# Grove_-_Button_x2.net
KiCad netlist of a schematic drawn in EAGLE
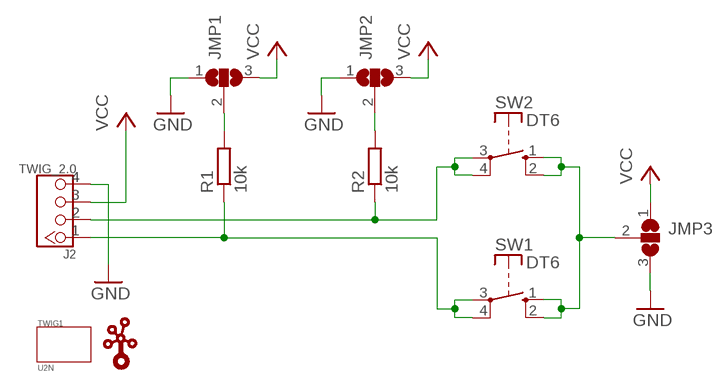
[diagram p0: schematic, sheet 1]

(export (version "E")
  (design (tool "Eeschema 10.0.6"))
  (components
    (comp (ref "J2")
      (value "TWIG_2.0")
      (footprint "eagle-import:2.0_1X4")
      (libsource (lib "eagle-import") (part "TWIG_2.0"))
    )
    (comp (ref "JMP1")
      (value "SJ2W")
      (footprint "eagle-import:SJ_2")
      (libsource (lib "eagle-import") (part "SJ2W"))
    )
    (comp (ref "JMP2")
      (value "SJ2W")
      (footprint "eagle-import:SJ_2")
      (libsource (lib "eagle-import") (part "SJ2W"))
    )
    (comp (ref "JMP3")
      (value "SJ2W")
      (footprint "eagle-import:SJ_2")
      (libsource (lib "eagle-import") (part "SJ2W"))
    )
    (comp (ref "R1")
      (value "10k")
      (footprint "eagle-import:R0805")
      (libsource (lib "eagle-import") (part "R-EU_R0805"))
    )
    (comp (ref "R2")
      (value "10k")
      (footprint "eagle-import:R0805")
      (libsource (lib "eagle-import") (part "R-EU_R0805"))
    )
    (comp (ref "SW1")
      (value "DT6")
      (footprint "eagle-import:DT6")
      (libsource (lib "eagle-import") (part "DT6"))
    )
    (comp (ref "SW2")
      (value "DT6")
      (footprint "eagle-import:DT6")
      (libsource (lib "eagle-import") (part "DT6"))
    )
    (comp (ref "TWIG1")
      (value "U2N")
      (footprint "eagle-import:U2N")
      (libsource (lib "eagle-import") (part "U2N"))
    )
    (comp (ref "U$1")
      (value "TWIGLOGOTWIGLOGO_SMALL")
      (footprint "eagle-import:TWIGLOGO_SMALL")
      (libsource (lib "eagle-import") (part "TWIGLOGOTWIGLOGO_SMALL"))
    )
  )
  (nets
    (net (code "1") (name "GND") (class "Default")
      (node (ref "J2") (pin "4") (pinfunction "4_4") (pintype "bidirectional"))
      (node (ref "JMP1") (pin "1") (pinfunction "1_1") (pintype "passive"))
      (node (ref "JMP2") (pin "1") (pinfunction "1_1") (pintype "passive"))
      (node (ref "JMP3") (pin "3") (pinfunction "3_3") (pintype "passive"))
    )
    (net (code "2") (name "Net-(J2-Pad1)") (class "Default")
      (node (ref "J2") (pin "1") (pinfunction "1_1") (pintype "bidirectional"))
      (node (ref "R1") (pin "1") (pinfunction "1_1") (pintype "passive"))
      (node (ref "SW1") (pin "3") (pinfunction "P_3") (pintype "passive"))
      (node (ref "SW1") (pin "4") (pinfunction "P_4") (pintype "passive"))
    )
    (net (code "3") (name "Net-(J2-Pad2)") (class "Default")
      (node (ref "J2") (pin "2") (pinfunction "2_2") (pintype "bidirectional"))
      (node (ref "R2") (pin "1") (pinfunction "1_1") (pintype "passive"))
      (node (ref "SW2") (pin "3") (pinfunction "P_3") (pintype "passive"))
      (node (ref "SW2") (pin "4") (pinfunction "P_4") (pintype "passive"))
    )
    (net (code "4") (name "Net-(JMP1-Pad2)") (class "Default")
      (node (ref "JMP1") (pin "2") (pinfunction "2_2") (pintype "passive"))
      (node (ref "R1") (pin "2") (pinfunction "2_2") (pintype "passive"))
    )
    (net (code "5") (name "Net-(JMP2-Pad2)") (class "Default")
      (node (ref "JMP2") (pin "2") (pinfunction "2_2") (pintype "passive"))
      (node (ref "R2") (pin "2") (pinfunction "2_2") (pintype "passive"))
    )
    (net (code "6") (name "Net-(JMP3-Pad2)") (class "Default")
      (node (ref "JMP3") (pin "2") (pinfunction "2_2") (pintype "passive"))
      (node (ref "SW1") (pin "1") (pinfunction "S_1") (pintype "passive"))
      (node (ref "SW1") (pin "2") (pinfunction "S_2") (pintype "passive"))
      (node (ref "SW2") (pin "1") (pinfunction "S_1") (pintype "passive"))
      (node (ref "SW2") (pin "2") (pinfunction "S_2") (pintype "passive"))
    )
    (net (code "7") (name "VCC") (class "Default")
      (node (ref "J2") (pin "3") (pinfunction "3_3") (pintype "bidirectional"))
      (node (ref "JMP1") (pin "3") (pinfunction "3_3") (pintype "passive"))
      (node (ref "JMP2") (pin "3") (pinfunction "3_3") (pintype "passive"))
      (node (ref "JMP3") (pin "1") (pinfunction "1_1") (pintype "passive"))
    )
  )
)
